# Mic.net
KiCad netlist of a schematic drawn in Altium Designer
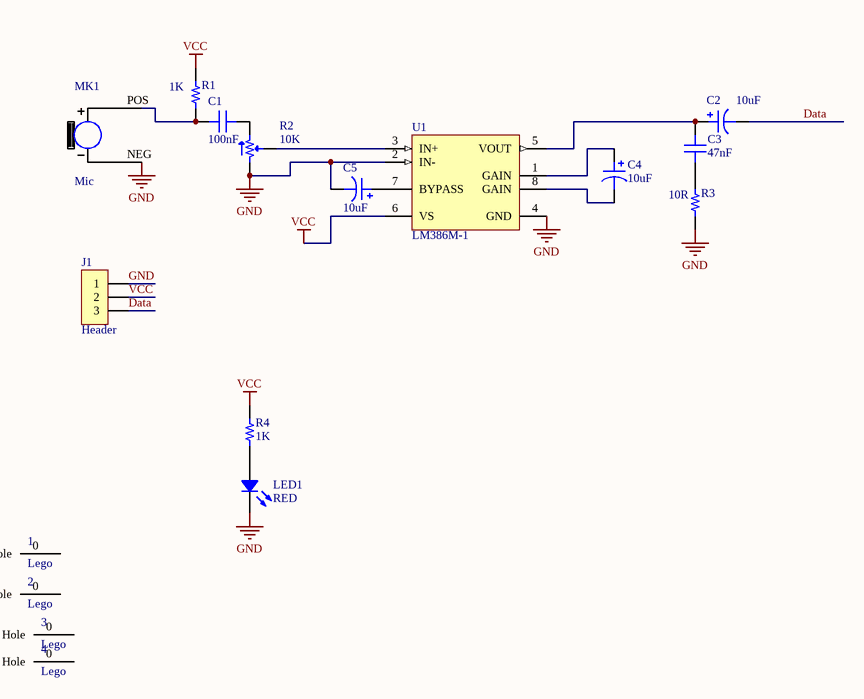
[diagram p0: Mic.SchDoc]

(export (version "E")
  (design (tool "Eeschema 10.0.6"))
  (components
    (comp (ref "1") (value "Lego") (footprint "Lego Hole") (libsource (lib "Connectors") (part "Lego")))
    (comp (ref "2") (value "Lego") (footprint "Lego Hole") (libsource (lib "Connectors") (part "Lego")))
    (comp (ref "3") (value "Lego") (footprint "Lego Hole") (libsource (lib "Connectors") (part "Lego")))
    (comp (ref "4") (value "Lego") (footprint "Lego Hole") (libsource (lib "Connectors") (part "Lego")))
    (comp (ref "C1")
      (value "100nF")
      (footprint "CAP 1206/3216")
      (description "SMT Capacitor")
      (libsource (lib "Cap_Res") (part "Capacitor"))
    )
    (comp (ref "C2")
      (value "10uF")
      (footprint "CAP ALUM 6.6MM")
      (description "SMT Polarised Capacitor")
      (libsource (lib "") (part "Polarised Capacitor_1"))
    )
    (comp (ref "C3")
      (value "47nF")
      (footprint "CAP 1206/3216")
      (description "SMT Capacitor")
      (libsource (lib "Cap_Res") (part "Capacitor"))
    )
    (comp (ref "C4")
      (value "10uF")
      (footprint "CAP ALUM 6.6MM")
      (description "SMT Polarised Capacitor")
      (libsource (lib "Cap_Res") (part "Polarised Capacitor"))
    )
    (comp (ref "C5")
      (value "10uF")
      (footprint "CAP ALUM 6.6MM")
      (description "SMT Polarised Capacitor")
      (libsource (lib "") (part "Polarised Capacitor_1"))
    )
    (comp (ref "J1")
      (value "Header")
      (footprint "MOLEX SDA-70553-3PIN")
      (libsource (lib "Connectors") (part "3 Pin"))
    )
    (comp (ref "LED1")
      (value "RED")
      (footprint "LED 1206/3216 RED")
      (description "Chip LED")
      (libsource (lib "Cap_Res") (part "LED"))
    )
    (comp (ref "MK1")
      (value "Mic")
      (footprint "Mic")
      (description "MIC COND ANALOG OMNI -38DB")
      (fields (field (name "MF") "PUI") (field (name "MP") "AOM-6738P-R"))
      (libsource (lib "Sensors") (part "Mic"))
    )
    (comp (ref "R1")
      (value "1K")
      (footprint "RES 1206/3216")
      (description "SMT Resistor")
      (libsource (lib "Cap_Res") (part "Resistor"))
    )
    (comp (ref "R2")
      (value "10K")
      (footprint "POT Panasonic EVM")
      (description "Potentiometer")
      (libsource (lib "Cap_Res") (part "Potentiometer"))
    )
    (comp (ref "R3")
      (value "10R")
      (footprint "RES 1206/3216")
      (description "SMT Resistor")
      (libsource (lib "Cap_Res") (part "Resistor"))
    )
    (comp (ref "R4")
      (value "1K")
      (footprint "RES 1206/3216")
      (description "SMT Resistor")
      (libsource (lib "Cap_Res") (part "Resistor"))
    )
    (comp (ref "U1")
      (value "LM386M-1")
      (footprint "M08A_M")
      (description "Low Voltage Audio Power Amplifier, 8-pin Narrow SOIC")
      (fields (field (name "MANUFACTURER") "National Semiconductor"))
      (libsource (lib "National Semiconductor Audio") (part "LM386M-1"))
    )
  )
  (nets
    (net (code "1") (name "/Data") (class "Default")
      (node (ref "C2") (pin "2") (pinfunction "2_2") (pintype "passive"))
      (node (ref "J1") (pin "3") (pinfunction "3_3") (pintype "passive"))
    )
    (net (code "2") (name "GND") (class "Default")
      (node (ref "C5") (pin "2") (pinfunction "2_2") (pintype "passive"))
      (node (ref "J1") (pin "1") (pinfunction "1_1") (pintype "passive"))
      (node (ref "LED1") (pin "2") (pinfunction "2_2") (pintype "passive"))
      (node (ref "MK1") (pin "NEG") (pinfunction "NEG_NEG") (pintype "passive"))
      (node (ref "R2") (pin "1") (pinfunction "1_1") (pintype "passive"))
      (node (ref "R3") (pin "1") (pinfunction "1_1") (pintype "passive"))
      (node (ref "U1") (pin "2") (pinfunction "IN-_2") (pintype "input"))
      (node (ref "U1") (pin "4") (pinfunction "GND_4") (pintype "power_in"))
    )
    (net (code "3") (name "Net-(C1-Pad1)") (class "Default")
      (node (ref "C1") (pin "1") (pinfunction "1_1") (pintype "passive"))
      (node (ref "MK1") (pin "POS") (pinfunction "POS_POS") (pintype "passive"))
      (node (ref "R1") (pin "1") (pinfunction "1_1") (pintype "passive"))
    )
    (net (code "4") (name "Net-(C1-Pad2)") (class "Default")
      (node (ref "C1") (pin "2") (pinfunction "2_2") (pintype "passive"))
      (node (ref "R2") (pin "3") (pinfunction "3_3") (pintype "passive"))
    )
    (net (code "5") (name "Net-(C3-Pad1)") (class "Default")
      (node (ref "C3") (pin "1") (pinfunction "1_1") (pintype "passive"))
      (node (ref "R3") (pin "2") (pinfunction "2_2") (pintype "passive"))
    )
    (net (code "6") (name "Net-(C4-Pad1)") (class "Default")
      (node (ref "C4") (pin "1") (pinfunction "1_1") (pintype "passive"))
      (node (ref "U1") (pin "1") (pinfunction "GAIN_1") (pintype "passive"))
    )
    (net (code "7") (name "Net-(C4-Pad2)") (class "Default")
      (node (ref "C4") (pin "2") (pinfunction "2_2") (pintype "passive"))
      (node (ref "U1") (pin "8") (pinfunction "GAIN_8") (pintype "passive"))
    )
    (net (code "8") (name "Net-(LED1-Pad1)") (class "Default")
      (node (ref "LED1") (pin "1") (pinfunction "1_1") (pintype "passive"))
      (node (ref "R4") (pin "1") (pinfunction "1_1") (pintype "passive"))
    )
    (net (code "9") (name "Net-(U1-BYPASS)") (class "Default")
      (node (ref "C5") (pin "1") (pinfunction "1_1") (pintype "passive"))
      (node (ref "U1") (pin "7") (pinfunction "BYPASS_7") (pintype "passive"))
    )
    (net (code "10") (name "Net-(U1-IN+)") (class "Default")
      (node (ref "R2") (pin "2") (pinfunction "2_2") (pintype "passive"))
      (node (ref "U1") (pin "3") (pinfunction "IN+_3") (pintype "input"))
    )
    (net (code "11") (name "Net-(U1-VOUT)") (class "Default")
      (node (ref "C2") (pin "1") (pinfunction "1_1") (pintype "passive"))
      (node (ref "C3") (pin "2") (pinfunction "2_2") (pintype "passive"))
      (node (ref "U1") (pin "5") (pinfunction "VOUT_5") (pintype "output"))
    )
    (net (code "12") (name "VCC") (class "Default")
      (node (ref "J1") (pin "2") (pinfunction "2_2") (pintype "passive"))
      (node (ref "R1") (pin "2") (pinfunction "2_2") (pintype "passive"))
      (node (ref "R4") (pin "2") (pinfunction "2_2") (pintype "passive"))
      (node (ref "U1") (pin "6") (pinfunction "VS_6") (pintype "power_in"))
    )
    (net (code "13") (name "unconnected-(1-Lego_Hole-Pad0)") (class "Default")
      (node (ref "1") (pin "0") (pinfunction "Lego_Hole_0") (pintype "passive"))
    )
    (net (code "14") (name "unconnected-(2-Lego_Hole-Pad0)") (class "Default")
      (node (ref "2") (pin "0") (pinfunction "Lego_Hole_0") (pintype "passive"))
    )
    (net (code "15") (name "unconnected-(3-Lego_Hole-Pad0)") (class "Default")
      (node (ref "3") (pin "0") (pinfunction "Lego_Hole_0") (pintype "passive"))
    )
    (net (code "16") (name "unconnected-(4-Lego_Hole-Pad0)") (class "Default")
      (node (ref "4") (pin "0") (pinfunction "Lego_Hole_0") (pintype "passive"))
    )
  )
)
